# mcu.net
KiCad netlist of a schematic drawn in Altium Designer
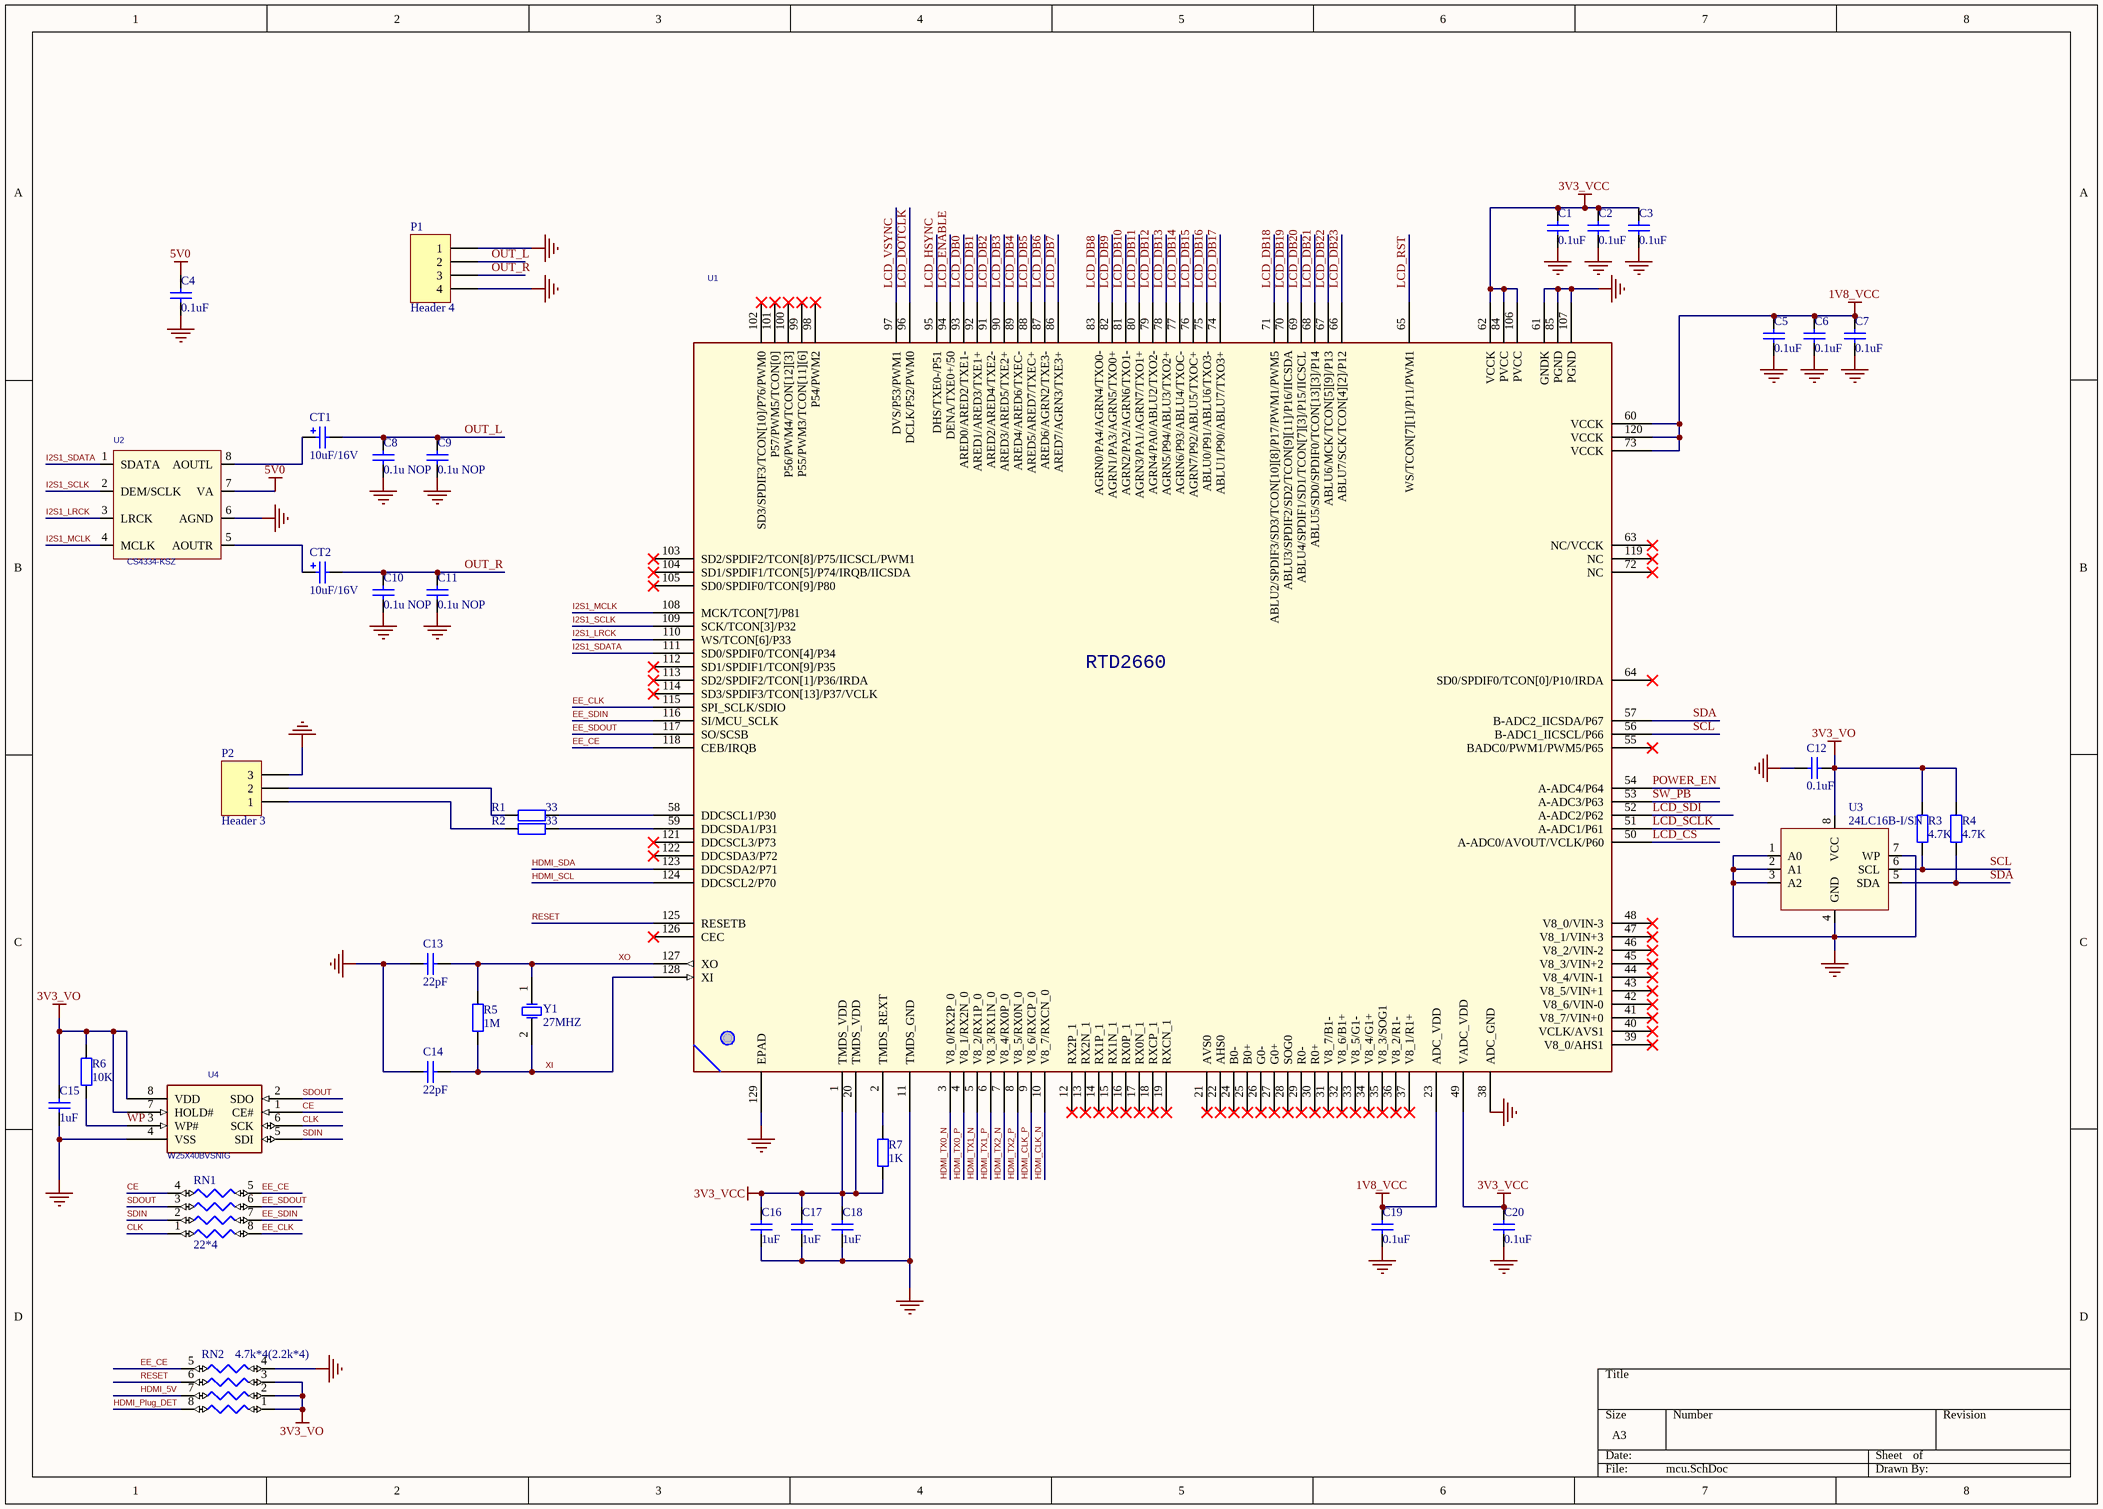
[diagram p0: mcu.SchDoc]

(export (version "E")
  (design (tool "Eeschema 10.0.6"))
  (components
    (comp (ref "C1")
      (value "0.1uF")
      (footprint "0603S-CAP")
      (description "50V/8.2u/0805")
      (fields (field (name "PUBLISHER") "Altium Limited"))
      (libsource (lib "Miscellaneous Devices") (part "Cap"))
    )
    (comp (ref "C2")
      (value "0.1uF")
      (footprint "0603S-CAP")
      (description "50V/8.2u/0805")
      (fields (field (name "PUBLISHER") "Altium Limited"))
      (libsource (lib "Miscellaneous Devices") (part "Cap"))
    )
    (comp (ref "C3")
      (value "0.1uF")
      (footprint "0603S-CAP")
      (description "50V/8.2u/0805")
      (fields (field (name "PUBLISHER") "Altium Limited"))
      (libsource (lib "Miscellaneous Devices") (part "Cap"))
    )
    (comp (ref "C4")
      (value "0.1uF")
      (footprint "0603S-CAP")
      (description "50V/8.2u/0805")
      (fields (field (name "PUBLISHER") "Altium Limited"))
      (libsource (lib "Miscellaneous Devices") (part "Cap"))
    )
    (comp (ref "C5")
      (value "0.1uF")
      (footprint "0603S-CAP")
      (description "50V/8.2u/0805")
      (fields (field (name "PUBLISHER") "Altium Limited"))
      (libsource (lib "Miscellaneous Devices") (part "Cap"))
    )
    (comp (ref "C6")
      (value "0.1uF")
      (footprint "0603S-CAP")
      (description "50V/8.2u/0805")
      (fields (field (name "PUBLISHER") "Altium Limited"))
      (libsource (lib "Miscellaneous Devices") (part "Cap"))
    )
    (comp (ref "C7")
      (value "0.1uF")
      (footprint "0603S-CAP")
      (description "50V/8.2u/0805")
      (fields (field (name "PUBLISHER") "Altium Limited"))
      (libsource (lib "Miscellaneous Devices") (part "Cap"))
    )
    (comp (ref "C8")
      (value "0.1u NOP")
      (footprint "0603S-CAP")
      (description "50V/8.2u/0805")
      (fields (field (name "PUBLISHER") "Altium Limited"))
      (libsource (lib "Miscellaneous Devices") (part "Cap"))
    )
    (comp (ref "C9")
      (value "0.1u NOP")
      (footprint "0603S-CAP")
      (description "50V/8.2u/0805")
      (fields (field (name "PUBLISHER") "Altium Limited"))
      (libsource (lib "Miscellaneous Devices") (part "Cap"))
    )
    (comp (ref "C10")
      (value "0.1u NOP")
      (footprint "0603S-CAP")
      (description "50V/8.2u/0805")
      (fields (field (name "PUBLISHER") "Altium Limited"))
      (libsource (lib "Miscellaneous Devices") (part "Cap"))
    )
    (comp (ref "C11")
      (value "0.1u NOP")
      (footprint "0603S-CAP")
      (description "50V/8.2u/0805")
      (fields (field (name "PUBLISHER") "Altium Limited"))
      (libsource (lib "Miscellaneous Devices") (part "Cap"))
    )
    (comp (ref "C12")
      (value "0.1uF")
      (footprint "0603S-CAP")
      (description "CAP SMT 0.1uF 16V X7R")
      (fields
        (field (name "2. MANUFACTURERE PART NUMBER") "C0805C104K4RACTU")
        (field (name "8. ALTERNATE PART") "any")
      )
      (libsource (lib "Peeple_eval") (part "CAP SMT 0.1uF 16V X7R"))
    )
    (comp (ref "C13")
      (value "22pF")
      (footprint "0603S-CAP")
      (description "50V/8.2u/0805")
      (fields (field (name "PUBLISHER") "Altium Limited"))
      (libsource (lib "Miscellaneous Devices") (part "Cap"))
    )
    (comp (ref "C14")
      (value "22pF")
      (footprint "0603S-CAP")
      (description "50V/8.2u/0805")
      (fields (field (name "PUBLISHER") "Altium Limited"))
      (libsource (lib "Miscellaneous Devices") (part "Cap"))
    )
    (comp (ref "C15")
      (value "1uF")
      (footprint "0603S-CAP")
      (description "50V/8.2u/0805")
      (fields (field (name "PUBLISHER") "Altium Limited"))
      (libsource (lib "Miscellaneous Devices") (part "Cap"))
    )
    (comp (ref "C16")
      (value "1uF")
      (footprint "0603S-CAP")
      (description "50V/8.2u/0805")
      (fields (field (name "PUBLISHER") "Altium Limited"))
      (libsource (lib "Miscellaneous Devices") (part "Cap"))
    )
    (comp (ref "C17")
      (value "1uF")
      (footprint "0603S-CAP")
      (description "50V/8.2u/0805")
      (fields (field (name "PUBLISHER") "Altium Limited"))
      (libsource (lib "Miscellaneous Devices") (part "Cap"))
    )
    (comp (ref "C18")
      (value "1uF")
      (footprint "0603S-CAP")
      (description "50V/8.2u/0805")
      (fields (field (name "PUBLISHER") "Altium Limited"))
      (libsource (lib "Miscellaneous Devices") (part "Cap"))
    )
    (comp (ref "C19")
      (value "0.1uF")
      (footprint "0603S-CAP")
      (description "50V/8.2u/0805")
      (fields (field (name "PUBLISHER") "Altium Limited"))
      (libsource (lib "Miscellaneous Devices") (part "Cap"))
    )
    (comp (ref "C20")
      (value "0.1uF")
      (footprint "0603S-CAP")
      (description "50V/8.2u/0805")
      (fields (field (name "PUBLISHER") "Altium Limited"))
      (libsource (lib "Miscellaneous Devices") (part "Cap"))
    )
    (comp (ref "CT1")
      (value "10uF/16V")
      (footprint "钽电容（A型）")
      (description "Polarized Capacitor (Axial)")
      (fields (field (name "PUBLISHER") "Altium Limited"))
      (libsource (lib "Miscellaneous Devices") (part "Cap Pol2"))
    )
    (comp (ref "CT2")
      (value "10uF/16V")
      (footprint "钽电容（A型）")
      (description "Polarized Capacitor (Axial)")
      (fields (field (name "PUBLISHER") "Altium Limited"))
      (libsource (lib "Miscellaneous Devices") (part "Cap Pol2"))
    )
    (comp (ref "P1")
      (value "Header 4")
      (footprint "PJ-342")
      (description "Header, 4-Pin")
      (fields (field (name "PUBLISHER") "Altium Limited"))
      (libsource (lib "Miscellaneous Connectors") (part "Header 4"))
    )
    (comp (ref "P2")
      (value "Header 3")
      (footprint "smt1X3")
      (description "Header, 3-Pin")
      (fields (field (name "PUBLISHER") "Altium Limited"))
      (libsource (lib "Miscellaneous Connectors") (part "Header 3"))
    )
    (comp (ref "R1")
      (value "33")
      (footprint "0603S-RES")
      (description "Resistor")
      (fields (field (name "PUBLISHER") "Altium Limited"))
      (libsource (lib "DM642") (part "Res2"))
    )
    (comp (ref "R2")
      (value "33")
      (footprint "0603S-RES")
      (description "Resistor")
      (fields (field (name "PUBLISHER") "Altium Limited"))
      (libsource (lib "DM642") (part "Res2"))
    )
    (comp (ref "R3")
      (value "4.7K")
      (footprint "0603S-RES")
      (description "Resistor")
      (fields (field (name "PUBLISHER") "Altium Limited"))
      (libsource (lib "") (part "Res2_1"))
    )
    (comp (ref "R4")
      (value "4.7K")
      (footprint "0603S-RES")
      (description "Resistor")
      (fields (field (name "PUBLISHER") "Altium Limited"))
      (libsource (lib "") (part "Res2_1"))
    )
    (comp (ref "R5")
      (value "1M")
      (footprint "0603S-RES")
      (description "Resistor")
      (fields (field (name "PUBLISHER") "Altium Limited"))
      (libsource (lib "") (part "Res2_1"))
    )
    (comp (ref "R6")
      (value "10K")
      (footprint "0603S-RES")
      (description "Resistor")
      (fields (field (name "PUBLISHER") "Altium Limited"))
      (libsource (lib "") (part "Res2_1"))
    )
    (comp (ref "R7")
      (value "1K")
      (footprint "0603S-RES")
      (description "Resistor")
      (fields (field (name "PUBLISHER") "Altium Limited"))
      (libsource (lib "") (part "Res2_1"))
    )
    (comp (ref "RN1") (value "22*4") (footprint "NC06-4") (libsource (lib "*") (part "RN4")))
    (comp (ref "RN2") (value "4.7k*4(2.2k*4)") (footprint "NC06-4") (libsource (lib "*") (part "RN4")))
    (comp (ref "U1")
      (value "RTD2660H")
      (footprint "LQFP128_P0_5_22X16_EPAD")
      (fields (field (name "PART NUMBER") "21-D004978"))
      (libsource (lib "*") (part "RTD2523_10"))
    )
    (comp (ref "U2")
      (value "CS4334-KSZ")
      (footprint "SOIC-8N")
      (fields (field (name "PART NUMBER") "19-D005021"))
      (libsource (lib "UC-410") (part "CS4334-KSZ"))
    )
    (comp (ref "U3")
      (value "24LC16B-I/SN")
      (footprint "SOIC-8N")
      (description "IC EEPROM 64KBIT 400KHZ 8SOIC")
      (fields
        (field (name "MANUFACTURER") "Microchip Technology")
        (field (name "MANUFACTURER PART NUMBER") "24LC64-I/SN")
      )
      (libsource (lib "Schlib1") (part "24LC64-I/SN"))
    )
    (comp (ref "U4")
      (value "W25X40BVSNIG")
      (footprint "SOIC-8N")
      (fields (field (name "PART NUMBER") "19-D004782"))
      (libsource (lib "*") (part "24C08_1"))
    )
    (comp (ref "Y1")
      (value "27MHZ")
      (footprint "XTAL-SMT")
      (description "Crystal, CRYSTAL 32.768KHZ 6PF SMD")
      (fields
        (field (name "2. MANUFACTURERE PART NUMBER") "ABS07-120-32.768KHZ-T")
        (field (name "4. SUPPLIER PART NUMBER") "535-11937-1-ND")
      )
      (libsource (lib "Peeple_eval") (part "XTAL 32.768KHZ"))
    )
  )
  (nets
    (net (code "1") (name "/CE") (class "Default")
      (node (ref "RN1") (pin "4") (pinfunction "4_4") (pintype "bidirectional"))
      (node (ref "U4") (pin "1") (pinfunction "CE#_1") (pintype "input"))
    )
    (net (code "2") (name "/CLK") (class "Default")
      (node (ref "RN1") (pin "1") (pinfunction "1_1") (pintype "bidirectional"))
      (node (ref "U4") (pin "6") (pinfunction "SCK_6") (pintype "bidirectional"))
    )
    (net (code "3") (name "/EE_CE") (class "Default")
      (node (ref "RN1") (pin "5") (pinfunction "5_5") (pintype "bidirectional"))
      (node (ref "RN2") (pin "5") (pinfunction "5_5") (pintype "bidirectional"))
      (node (ref "U1") (pin "118") (pinfunction "CEB/IRQB_118") (pintype "passive"))
    )
    (net (code "4") (name "/EE_CLK") (class "Default")
      (node (ref "RN1") (pin "8") (pinfunction "8_8") (pintype "bidirectional"))
      (node (ref "U1") (pin "115") (pinfunction "SPI_SCLK/SDIO_115") (pintype "passive"))
    )
    (net (code "5") (name "/EE_SDIN") (class "Default")
      (node (ref "RN1") (pin "7") (pinfunction "7_7") (pintype "bidirectional"))
      (node (ref "U1") (pin "116") (pinfunction "SI/MCU_SCLK_116") (pintype "passive"))
    )
    (net (code "6") (name "/EE_SDOUT") (class "Default")
      (node (ref "RN1") (pin "6") (pinfunction "6_6") (pintype "bidirectional"))
      (node (ref "U1") (pin "117") (pinfunction "SO/SCSB_117") (pintype "passive"))
    )
    (net (code "7") (name "/HDMI_5V") (class "Default")
      (node (ref "RN2") (pin "7") (pinfunction "7_7") (pintype "bidirectional"))
    )
    (net (code "8") (name "/HDMI_CLK_N") (class "Default")
      (node (ref "U1") (pin "10") (pinfunction "V8_7/RXCN_0_10") (pintype "passive"))
    )
    (net (code "9") (name "/HDMI_CLK_P") (class "Default")
      (node (ref "U1") (pin "9") (pinfunction "V8_6/RXCP_0_9") (pintype "passive"))
    )
    (net (code "10") (name "/HDMI_Plug_DET") (class "Default")
      (node (ref "RN2") (pin "8") (pinfunction "8_8") (pintype "bidirectional"))
    )
    (net (code "11") (name "/HDMI_SCL") (class "Default")
      (node (ref "U1") (pin "124") (pinfunction "DDCSCL2/P70_124") (pintype "passive"))
    )
    (net (code "12") (name "/HDMI_SDA") (class "Default")
      (node (ref "U1") (pin "123") (pinfunction "DDCSDA2/P71_123") (pintype "passive"))
    )
    (net (code "13") (name "/HDMI_TX0_N") (class "Default")
      (node (ref "U1") (pin "3") (pinfunction "V8_0/RX2P_0_3") (pintype "passive"))
    )
    (net (code "14") (name "/HDMI_TX0_P") (class "Default")
      (node (ref "U1") (pin "4") (pinfunction "V8_1/RX2N_0_4") (pintype "passive"))
    )
    (net (code "15") (name "/HDMI_TX1_N") (class "Default")
      (node (ref "U1") (pin "5") (pinfunction "V8_2/RX1P_0_5") (pintype "passive"))
    )
    (net (code "16") (name "/HDMI_TX1_P") (class "Default")
      (node (ref "U1") (pin "6") (pinfunction "V8_3/RX1N_0_6") (pintype "passive"))
    )
    (net (code "17") (name "/HDMI_TX2_N") (class "Default")
      (node (ref "U1") (pin "7") (pinfunction "V8_4/RX0P_0_7") (pintype "passive"))
    )
    (net (code "18") (name "/HDMI_TX2_P") (class "Default")
      (node (ref "U1") (pin "8") (pinfunction "V8_5/RX0N_0_8") (pintype "passive"))
    )
    (net (code "19") (name "/I2S1_LRCK") (class "Default")
      (node (ref "U1") (pin "110") (pinfunction "WS/TCON[6]/P33_110") (pintype "passive"))
      (node (ref "U2") (pin "3") (pinfunction "LRCK_3") (pintype "passive"))
    )
    (net (code "20") (name "/I2S1_MCLK") (class "Default")
      (node (ref "U1") (pin "108") (pinfunction "MCK/TCON[7]/P81_108") (pintype "passive"))
      (node (ref "U2") (pin "4") (pinfunction "MCLK_4") (pintype "passive"))
    )
    (net (code "21") (name "/I2S1_SCLK") (class "Default")
      (node (ref "U1") (pin "109") (pinfunction "SCK/TCON[3]/P32_109") (pintype "passive"))
      (node (ref "U2") (pin "2") (pinfunction "DEM/SCLK_2") (pintype "passive"))
    )
    (net (code "22") (name "/I2S1_SDATA") (class "Default")
      (node (ref "U1") (pin "111") (pinfunction "SD0/SPDIF0/TCON[4]/P34_111") (pintype "passive"))
      (node (ref "U2") (pin "1") (pinfunction "SDATA_1") (pintype "passive"))
    )
    (net (code "23") (name "/LCD_CS") (class "Default")
      (node (ref "U1") (pin "50") (pinfunction "A-ADC0/AVOUT/VCLK/P60_50") (pintype "passive"))
    )
    (net (code "24") (name "/LCD_DB0") (class "Default")
      (node (ref "U1") (pin "93") (pinfunction "ARED0/ARED2/TXE1-_93") (pintype "passive"))
    )
    (net (code "25") (name "/LCD_DB1") (class "Default")
      (node (ref "U1") (pin "92") (pinfunction "ARED1/ARED3/TXE1+_92") (pintype "passive"))
    )
    (net (code "26") (name "/LCD_DB2") (class "Default")
      (node (ref "U1") (pin "91") (pinfunction "ARED2/ARED4/TXE2-_91") (pintype "passive"))
    )
    (net (code "27") (name "/LCD_DB3") (class "Default")
      (node (ref "U1") (pin "90") (pinfunction "ARED3/ARED5/TXE2+_90") (pintype "passive"))
    )
    (net (code "28") (name "/LCD_DB4") (class "Default")
      (node (ref "U1") (pin "89") (pinfunction "ARED4/ARED6/TXEC-_89") (pintype "passive"))
    )
    (net (code "29") (name "/LCD_DB5") (class "Default")
      (node (ref "U1") (pin "88") (pinfunction "ARED5/ARED7/TXEC+_88") (pintype "passive"))
    )
    (net (code "30") (name "/LCD_DB6") (class "Default")
      (node (ref "U1") (pin "87") (pinfunction "ARED6/AGRN2/TXE3-_87") (pintype "passive"))
    )
    (net (code "31") (name "/LCD_DB7") (class "Default")
      (node (ref "U1") (pin "86") (pinfunction "ARED7/AGRN3/TXE3+_86") (pintype "passive"))
    )
    (net (code "32") (name "/LCD_DB8") (class "Default")
      (node (ref "U1") (pin "83") (pinfunction "AGRN0/PA4/AGRN4/TXO0-_83") (pintype "passive"))
    )
    (net (code "33") (name "/LCD_DB9") (class "Default")
      (node (ref "U1") (pin "82") (pinfunction "AGRN1/PA3/AGRN5/TXO0+_82") (pintype "passive"))
    )
    (net (code "34") (name "/LCD_DB10") (class "Default")
      (node (ref "U1") (pin "81") (pinfunction "AGRN2/PA2/AGRN6/TXO1-_81") (pintype "passive"))
    )
    (net (code "35") (name "/LCD_DB11") (class "Default")
      (node (ref "U1") (pin "80") (pinfunction "AGRN3/PA1/AGRN7/TXO1+_80") (pintype "passive"))
    )
    (net (code "36") (name "/LCD_DB12") (class "Default")
      (node (ref "U1") (pin "79") (pinfunction "AGRN4/PA0/ABLU2/TXO2-_79") (pintype "passive"))
    )
    (net (code "37") (name "/LCD_DB13") (class "Default")
      (node (ref "U1") (pin "78") (pinfunction "AGRN5/P94/ABLU3/TXO2+_78") (pintype "passive"))
    )
    (net (code "38") (name "/LCD_DB14") (class "Default")
      (node (ref "U1") (pin "77") (pinfunction "AGRN6/P93/ABLU4/TXOC-_77") (pintype "passive"))
    )
    (net (code "39") (name "/LCD_DB15") (class "Default")
      (node (ref "U1") (pin "76") (pinfunction "AGRN7/P92/ABLU5/TXOC+_76") (pintype "passive"))
    )
    (net (code "40") (name "/LCD_DB16") (class "Default")
      (node (ref "U1") (pin "75") (pinfunction "ABLU0/P91/ABLU6/TXO3-_75") (pintype "passive"))
    )
    (net (code "41") (name "/LCD_DB17") (class "Default")
      (node (ref "U1") (pin "74") (pinfunction "ABLU1/P90/ABLU7/TXO3+_74") (pintype "passive"))
    )
    (net (code "42") (name "/LCD_DB18") (class "Default")
      (node (ref "U1") (pin "71") (pinfunction "ABLU2/SPDIF3/SD3/TCON[10][8]/P17/PWM1/PWM5_71") (pintype "passive"))
    )
    (net (code "43") (name "/LCD_DB19") (class "Default")
      (node (ref "U1") (pin "70") (pinfunction "ABLU3/SPDIF2/SD2/TCON[9][11]/P16/IICSDA_70") (pintype "passive"))
    )
    (net (code "44") (name "/LCD_DB20") (class "Default")
      (node (ref "U1") (pin "69") (pinfunction "ABLU4/SPDIF1/SD1/TCON[7][3]/P15/IICSCL_69") (pintype "passive"))
    )
    (net (code "45") (name "/LCD_DB21") (class "Default")
      (node (ref "U1") (pin "68") (pinfunction "ABLU5/SD0/SPDIF0/TCON[13][3]/P14_68") (pintype "passive"))
    )
    (net (code "46") (name "/LCD_DB22") (class "Default")
      (node (ref "U1") (pin "67") (pinfunction "ABLU6/MCK/TCON[5][9]/P13_67") (pintype "passive"))
    )
    (net (code "47") (name "/LCD_DB23") (class "Default")
      (node (ref "U1") (pin "66") (pinfunction "ABLU7/SCK/TCON[4][2]/P12_66") (pintype "passive"))
    )
    (net (code "48") (name "/LCD_DOTCLK") (class "Default")
      (node (ref "U1") (pin "96") (pinfunction "DCLK/P52/PWM0_96") (pintype "passive"))
    )
    (net (code "49") (name "/LCD_ENABLE") (class "Default")
      (node (ref "U1") (pin "94") (pinfunction "DENA/TXE0+/50_94") (pintype "passive"))
    )
    (net (code "50") (name "/LCD_HSYNC") (class "Default")
      (node (ref "U1") (pin "95") (pinfunction "DHS/TXE0-/P51_95") (pintype "passive"))
    )
    (net (code "51") (name "/LCD_RST") (class "Default")
      (node (ref "U1") (pin "65") (pinfunction "WS/TCON[7][1]/P11/PWM1_65") (pintype "passive"))
    )
    (net (code "52") (name "/LCD_SCLK") (class "Default")
      (node (ref "U1") (pin "51") (pinfunction "A-ADC1/P61_51") (pintype "passive"))
    )
    (net (code "53") (name "/LCD_SDI") (class "Default")
      (node (ref "U1") (pin "52") (pinfunction "A-ADC2/P62_52") (pintype "passive"))
    )
    (net (code "54") (name "/LCD_VSYNC") (class "Default")
      (node (ref "U1") (pin "97") (pinfunction "DVS/P53/PWM1_97") (pintype "passive"))
    )
    (net (code "55") (name "/OUT_L") (class "Default")
      (node (ref "C8") (pin "2") (pinfunction "2_2") (pintype "passive"))
      (node (ref "C9") (pin "2") (pinfunction "2_2") (pintype "passive"))
      (node (ref "CT1") (pin "2") (pinfunction "2_2") (pintype "passive"))
      (node (ref "P1") (pin "2") (pinfunction "2_2") (pintype "passive"))
    )
    (net (code "56") (name "/OUT_R") (class "Default")
      (node (ref "C10") (pin "2") (pinfunction "2_2") (pintype "passive"))
      (node (ref "C11") (pin "2") (pinfunction "2_2") (pintype "passive"))
      (node (ref "CT2") (pin "2") (pinfunction "2_2") (pintype "passive"))
      (node (ref "P1") (pin "3") (pinfunction "3_3") (pintype "passive"))
    )
    (net (code "57") (name "/POWER_EN") (class "Default")
      (node (ref "U1") (pin "54") (pinfunction "A-ADC4/P64_54") (pintype "passive"))
    )
    (net (code "58") (name "/RESET") (class "Default")
      (node (ref "RN2") (pin "6") (pinfunction "6_6") (pintype "bidirectional"))
      (node (ref "U1") (pin "125") (pinfunction "RESETB_125") (pintype "passive"))
    )
    (net (code "59") (name "/SCL") (class "Default")
      (node (ref "R3") (pin "1") (pinfunction "1_1") (pintype "passive"))
      (node (ref "U1") (pin "56") (pinfunction "B-ADC1_IICSCL/P66_56") (pintype "passive"))
      (node (ref "U3") (pin "6") (pinfunction "SCL_6") (pintype "passive"))
    )
    (net (code "60") (name "/SDA") (class "Default")
      (node (ref "R4") (pin "1") (pinfunction "1_1") (pintype "passive"))
      (node (ref "U1") (pin "57") (pinfunction "B-ADC2_IICSDA/P67_57") (pintype "passive"))
      (node (ref "U3") (pin "5") (pinfunction "SDA_5") (pintype "passive"))
    )
    (net (code "61") (name "/SDIN") (class "Default")
      (node (ref "RN1") (pin "2") (pinfunction "2_2") (pintype "bidirectional"))
      (node (ref "U4") (pin "5") (pinfunction "SDI_5") (pintype "bidirectional"))
    )
    (net (code "62") (name "/SDOUT") (class "Default")
      (node (ref "RN1") (pin "3") (pinfunction "3_3") (pintype "bidirectional"))
      (node (ref "U4") (pin "2") (pinfunction "SDO_2") (pintype "input"))
    )
    (net (code "63") (name "/SW_PB") (class "Default")
      (node (ref "U1") (pin "53") (pinfunction "A-ADC3/P63_53") (pintype "passive"))
    )
    (net (code "64") (name "/WP") (class "Default")
      (node (ref "R6") (pin "1") (pinfunction "1_1") (pintype "passive"))
      (node (ref "U4") (pin "3") (pinfunction "WP#_3") (pintype "input"))
    )
    (net (code "65") (name "/XI") (class "Default")
      (node (ref "C14") (pin "1") (pinfunction "1_1") (pintype "passive"))
      (node (ref "R5") (pin "1") (pinfunction "1_1") (pintype "passive"))
      (node (ref "U1") (pin "128") (pinfunction "XI_128") (pintype "input"))
      (node (ref "Y1") (pin "2") (pinfunction "OSC2_2") (pintype "passive"))
    )
    (net (code "66") (name "/XO") (class "Default")
      (node (ref "C13") (pin "1") (pinfunction "1_1") (pintype "passive"))
      (node (ref "R5") (pin "2") (pinfunction "2_2") (pintype "passive"))
      (node (ref "U1") (pin "127") (pinfunction "XO_127") (pintype "output"))
      (node (ref "Y1") (pin "1") (pinfunction "OSC1_1") (pintype "passive"))
    )
    (net (code "67") (name "1V8_VCC") (class "Default")
      (node (ref "C19") (pin "2") (pinfunction "2_2") (pintype "passive"))
      (node (ref "C5") (pin "2") (pinfunction "2_2") (pintype "passive"))
      (node (ref "C6") (pin "2") (pinfunction "2_2") (pintype "passive"))
      (node (ref "C7") (pin "2") (pinfunction "2_2") (pintype "passive"))
      (node (ref "U1") (pin "120") (pinfunction "VCCK_120") (pintype "power_in"))
      (node (ref "U1") (pin "23") (pinfunction "ADC_VDD_23") (pintype "power_in"))
      (node (ref "U1") (pin "60") (pinfunction "VCCK_60") (pintype "power_in"))
      (node (ref "U1") (pin "73") (pinfunction "VCCK_73") (pintype "power_in"))
    )
    (net (code "68") (name "3V3_VCC") (class "Default")
      (node (ref "C1") (pin "2") (pinfunction "2_2") (pintype "passive"))
      (node (ref "C16") (pin "2") (pinfunction "2_2") (pintype "passive"))
      (node (ref "C17") (pin "2") (pinfunction "2_2") (pintype "passive"))
      (node (ref "C18") (pin "2") (pinfunction "2_2") (pintype "passive"))
      (node (ref "C2") (pin "2") (pinfunction "2_2") (pintype "passive"))
      (node (ref "C20") (pin "2") (pinfunction "2_2") (pintype "passive"))
      (node (ref "C3") (pin "2") (pinfunction "2_2") (pintype "passive"))
      (node (ref "R7") (pin "1") (pinfunction "1_1") (pintype "passive"))
      (node (ref "U1") (pin "1") (pinfunction "TMDS_VDD_1") (pintype "power_in"))
      (node (ref "U1") (pin "106") (pinfunction "PVCC_106") (pintype "power_in"))
      (node (ref "U1") (pin "20") (pinfunction "TMDS_VDD_20") (pintype "power_in"))
      (node (ref "U1") (pin "49") (pinfunction "VADC_VDD_49") (pintype "power_in"))
      (node (ref "U1") (pin "62") (pinfunction "VCCK_62") (pintype "power_in"))
      (node (ref "U1") (pin "84") (pinfunction "PVCC_84") (pintype "power_in"))
    )
    (net (code "69") (name "3V3_VO") (class "Default")
      (node (ref "C12") (pin "2") (pinfunction "2_2") (pintype "passive"))
      (node (ref "C15") (pin "2") (pinfunction "2_2") (pintype "passive"))
      (node (ref "R3") (pin "2") (pinfunction "2_2") (pintype "passive"))
      (node (ref "R4") (pin "2") (pinfunction "2_2") (pintype "passive"))
      (node (ref "R6") (pin "2") (pinfunction "2_2") (pintype "passive"))
      (node (ref "RN2") (pin "1") (pinfunction "1_1") (pintype "bidirectional"))
      (node (ref "RN2") (pin "2") (pinfunction "2_2") (pintype "bidirectional"))
      (node (ref "RN2") (pin "3") (pinfunction "3_3") (pintype "bidirectional"))
      (node (ref "U3") (pin "8") (pinfunction "VCC_8") (pintype "passive"))
      (node (ref "U4") (pin "7") (pinfunction "HOLD#_7") (pintype "input"))
      (node (ref "U4") (pin "8") (pinfunction "VDD_8") (pintype "power_in"))
    )
    (net (code "70") (name "5V0") (class "Default")
      (node (ref "C4") (pin "2") (pinfunction "2_2") (pintype "passive"))
      (node (ref "U2") (pin "7") (pinfunction "VA_7") (pintype "passive"))
    )
    (net (code "71") (name "GND") (class "Default")
      (node (ref "C1") (pin "1") (pinfunction "1_1") (pintype "passive"))
      (node (ref "C10") (pin "1") (pinfunction "1_1") (pintype "passive"))
      (node (ref "C11") (pin "1") (pinfunction "1_1") (pintype "passive"))
      (node (ref "C12") (pin "1") (pinfunction "1_1") (pintype "passive"))
      (node (ref "C13") (pin "2") (pinfunction "2_2") (pintype "passive"))
      (node (ref "C14") (pin "2") (pinfunction "2_2") (pintype "passive"))
      (node (ref "C15") (pin "1") (pinfunction "1_1") (pintype "passive"))
      (node (ref "C16") (pin "1") (pinfunction "1_1") (pintype "passive"))
      (node (ref "C17") (pin "1") (pinfunction "1_1") (pintype "passive"))
      (node (ref "C18") (pin "1") (pinfunction "1_1") (pintype "passive"))
      (node (ref "C19") (pin "1") (pinfunction "1_1") (pintype "passive"))
      (node (ref "C2") (pin "1") (pinfunction "1_1") (pintype "passive"))
      (node (ref "C20") (pin "1") (pinfunction "1_1") (pintype "passive"))
      (node (ref "C3") (pin "1") (pinfunction "1_1") (pintype "passive"))
      (node (ref "C4") (pin "1") (pinfunction "1_1") (pintype "passive"))
      (node (ref "C5") (pin "1") (pinfunction "1_1") (pintype "passive"))
      (node (ref "C6") (pin "1") (pinfunction "1_1") (pintype "passive"))
      (node (ref "C7") (pin "1") (pinfunction "1_1") (pintype "passive"))
      (node (ref "C8") (pin "1") (pinfunction "1_1") (pintype "passive"))
      (node (ref "C9") (pin "1") (pinfunction "1_1") (pintype "passive"))
      (node (ref "P1") (pin "1") (pinfunction "1_1") (pintype "passive"))
      (node (ref "P1") (pin "4") (pinfunction "4_4") (pintype "passive"))
      (node (ref "P2") (pin "3") (pinfunction "3_3") (pintype "passive"))
      (node (ref "RN2") (pin "4") (pinfunction "4_4") (pintype "bidirectional"))
      (node (ref "U1") (pin "107") (pinfunction "PGND_107") (pintype "power_in"))
      (node (ref "U1") (pin "11") (pinfunction "TMDS_GND_11") (pintype "power_in"))
      (node (ref "U1") (pin "129") (pinfunction "EPAD_129") (pintype "passive"))
      (node (ref "U1") (pin "38") (pinfunction "ADC_GND_38") (pintype "power_in"))
      (node (ref "U1") (pin "61") (pinfunction "GNDK_61") (pintype "power_in"))
      (node (ref "U1") (pin "85") (pinfunction "PGND_85") (pintype "power_in"))
      (node (ref "U2") (pin "6") (pinfunction "AGND_6") (pintype "passive"))
      (node (ref "U3") (pin "1") (pinfunction "A0_1") (pintype "passive"))
      (node (ref "U3") (pin "2") (pinfunction "A1_2") (pintype "passive"))
      (node (ref "U3") (pin "3") (pinfunction "A2_3") (pintype "passive"))
      (node (ref "U3") (pin "4") (pinfunction "GND_4") (pintype "passive"))
      (node (ref "U3") (pin "7") (pinfunction "WP_7") (pintype "passive"))
      (node (ref "U4") (pin "4") (pinfunction "VSS_4") (pintype "power_in"))
    )
    (net (code "72") (name "Net-(P2-Pad1)") (class "Default")
      (node (ref "P2") (pin "1") (pinfunction "1_1") (pintype "passive"))
      (node (ref "R2") (pin "2") (pinfunction "2_2") (pintype "passive"))
    )
    (net (code "73") (name "Net-(P2-Pad2)") (class "Default")
      (node (ref "P2") (pin "2") (pinfunction "2_2") (pintype "passive"))
      (node (ref "R1") (pin "2") (pinfunction "2_2") (pintype "passive"))
    )
    (net (code "74") (name "Net-(U1-DDCSCL1{slash}P30)") (class "Default")
      (node (ref "R1") (pin "1") (pinfunction "1_1") (pintype "passive"))
      (node (ref "U1") (pin "58") (pinfunction "DDCSCL1/P30_58") (pintype "passive"))
    )
    (net (code "75") (name "Net-(U1-DDCSDA1{slash}P31)") (class "Default")
      (node (ref "R2") (pin "1") (pinfunction "1_1") (pintype "passive"))
      (node (ref "U1") (pin "59") (pinfunction "DDCSDA1/P31_59") (pintype "passive"))
    )
    (net (code "76") (name "Net-(U1-TMDS_REXT)") (class "Default")
      (node (ref "R7") (pin "2") (pinfunction "2_2") (pintype "passive"))
      (node (ref "U1") (pin "2") (pinfunction "TMDS_REXT_2") (pintype "passive"))
    )
    (net (code "77") (name "Net-(U2-AOUTL)") (class "Default")
      (node (ref "CT1") (pin "1") (pinfunction "1_1") (pintype "passive"))
      (node (ref "U2") (pin "8") (pinfunction "AOUTL_8") (pintype "passive"))
    )
    (net (code "78") (name "Net-(U2-AOUTR)") (class "Default")
      (node (ref "CT2") (pin "1") (pinfunction "1_1") (pintype "passive"))
      (node (ref "U2") (pin "5") (pinfunction "AOUTR_5") (pintype "passive"))
    )
    (net (code "79") (name "unconnected-(U1-AHS0-Pad22)") (class "Default")
      (node (ref "U1") (pin "22") (pinfunction "AHS0_22") (pintype "passive+no_connect"))
    )
    (net (code "80") (name "unconnected-(U1-AVS0-Pad21)") (class "Default")
      (node (ref "U1") (pin "21") (pinfunction "AVS0_21") (pintype "passive+no_connect"))
    )
    (net (code "81") (name "unconnected-(U1-B0+-Pad25)") (class "Default")
      (node (ref "U1") (pin "25") (pinfunction "B0+_25") (pintype "passive+no_connect"))
    )
    (net (code "82") (name "unconnected-(U1-B0--Pad24)") (class "Default")
      (node (ref "U1") (pin "24") (pinfunction "B0-_24") (pintype "passive+no_connect"))
    )
    (net (code "83") (name "unconnected-(U1-BADC0{slash}PWM1{slash}PWM5{slash}P65-Pad55)") (class "Default")
      (node (ref "U1") (pin "55") (pinfunction "BADC0/PWM1/PWM5/P65_55") (pintype "passive+no_connect"))
    )
    (net (code "84") (name "unconnected-(U1-CEC-Pad126)") (class "Default")
      (node (ref "U1") (pin "126") (pinfunction "CEC_126") (pintype "passive+no_connect"))
    )
    (net (code "85") (name "unconnected-(U1-DDCSCL3{slash}P73-Pad121)") (class "Default")
      (node (ref "U1") (pin "121") (pinfunction "DDCSCL3/P73_121") (pintype "passive+no_connect"))
    )
    (net (code "86") (name "unconnected-(U1-DDCSDA3{slash}P72-Pad122)") (class "Default")
      (node (ref "U1") (pin "122") (pinfunction "DDCSDA3/P72_122") (pintype "passive+no_connect"))
    )
    (net (code "87") (name "unconnected-(U1-G0+-Pad27)") (class "Default")
      (node (ref "U1") (pin "27") (pinfunction "G0+_27") (pintype "passive+no_connect"))
    )
    (net (code "88") (name "unconnected-(U1-G0--Pad26)") (class "Default")
      (node (ref "U1") (pin "26") (pinfunction "G0-_26") (pintype "passive+no_connect"))
    )
    (net (code "89") (name "unconnected-(U1-NC-Pad72)") (class "Default")
      (node (ref "U1") (pin "72") (pinfunction "NC_72") (pintype "passive+no_connect"))
    )
    (net (code "90") (name "unconnected-(U1-NC-Pad119)") (class "Default")
      (node (ref "U1") (pin "119") (pinfunction "NC_119") (pintype "passive+no_connect"))
    )
    (net (code "91") (name "unconnected-(U1-NC{slash}VCCK-Pad63)") (class "Default")
      (node (ref "U1") (pin "63") (pinfunction "NC/VCCK_63") (pintype "passive+no_connect"))
    )
    (net (code "92") (name "unconnected-(U1-P54{slash}PWM2-Pad98)") (class "Default")
      (node (ref "U1") (pin "98") (pinfunction "P54/PWM2_98") (pintype "passive+no_connect"))
    )
    (net (code "93") (name "unconnected-(U1-P55{slash}PWM3{slash}TCON[11][6]-Pad99)") (class "Default")
      (node (ref "U1") (pin "99") (pinfunction "P55/PWM3/TCON[11][6]_99") (pintype "passive+no_connect"))
    )
    (net (code "94") (name "unconnected-(U1-P56{slash}PWM4{slash}TCON[12][3]-Pad100)") (class "Default")
      (node (ref "U1") (pin "100") (pinfunction "P56/PWM4/TCON[12][3]_100") (pintype "passive+no_connect"))
    )
    (net (code "95") (name "unconnected-(U1-P57{slash}PWM5{slash}TCON[0]-Pad101)") (class "Default")
      (node (ref "U1") (pin "101") (pinfunction "P57/PWM5/TCON[0]_101") (pintype "passive+no_connect"))
    )
    (net (code "96") (name "unconnected-(U1-R0+-Pad30)") (class "Default")
      (node (ref "U1") (pin "30") (pinfunction "R0+_30") (pintype "passive+no_connect"))
    )
    (net (code "97") (name "unconnected-(U1-R0--Pad29)") (class "Default")
      (node (ref "U1") (pin "29") (pinfunction "R0-_29") (pintype "passive+no_connect"))
    )
    (net (code "98") (name "unconnected-(U1-RX0N_1-Pad17)") (class "Default")
      (node (ref "U1") (pin "17") (pinfunction "RX0N_1_17") (pintype "passive+no_connect"))
    )
    (net (code "99") (name "unconnected-(U1-RX0P_1-Pad16)") (class "Default")
      (node (ref "U1") (pin "16") (pinfunction "RX0P_1_16") (pintype "passive+no_connect"))
    )
    (net (code "100") (name "unconnected-(U1-RX1N_1-Pad15)") (class "Default")
      (node (ref "U1") (pin "15") (pinfunction "RX1N_1_15") (pintype "passive+no_connect"))
    )
    (net (code "101") (name "unconnected-(U1-RX1P_1-Pad14)") (class "Default")
      (node (ref "U1") (pin "14") (pinfunction "RX1P_1_14") (pintype "passive+no_connect"))
    )
    (net (code "102") (name "unconnected-(U1-RX2N_1-Pad13)") (class "Default")
      (node (ref "U1") (pin "13") (pinfunction "RX2N_1_13") (pintype "passive+no_connect"))
    )
    (net (code "103") (name "unconnected-(U1-RX2P_1-Pad12)") (class "Default")
      (node (ref "U1") (pin "12") (pinfunction "RX2P_1_12") (pintype "passive+no_connect"))
    )
    (net (code "104") (name "unconnected-(U1-RXCN_1-Pad19)") (class "Default")
      (node (ref "U1") (pin "19") (pinfunction "RXCN_1_19") (pintype "passive+no_connect"))
    )
    (net (code "105") (name "unconnected-(U1-RXCP_1-Pad18)") (class "Default")
      (node (ref "U1") (pin "18") (pinfunction "RXCP_1_18") (pintype "passive+no_connect"))
    )
    (net (code "106") (name "unconnected-(U1-SD0{slash}SPDIF0{slash}TCON[0]{slash}P10{slash}IRDA-Pad64)") (class "Default")
      (node (ref "U1") (pin "64") (pinfunction "SD0/SPDIF0/TCON[0]/P10/IRDA_64") (pintype "passive+no_connect"))
    )
    (net (code "107") (name "unconnected-(U1-SD0{slash}SPDIF0{slash}TCON[9]{slash}P80-Pad105)") (class "Default")
      (node (ref "U1") (pin "105") (pinfunction "SD0/SPDIF0/TCON[9]/P80_105") (pintype "passive+no_connect"))
    )
    (net (code "108") (name "unconnected-(U1-SD1{slash}SPDIF1{slash}TCON[5]{slash}P74{slash}IRQB{slash}IICSDA-Pad104)") (class "Default")
      (node (ref "U1") (pin "104") (pinfunction "SD1/SPDIF1/TCON[5]/P74/IRQB/IICSDA_104") (pintype "passive+no_connect"))
    )
    (net (code "109") (name "unconnected-(U1-SD1{slash}SPDIF1{slash}TCON[9]{slash}P35-Pad112)") (class "Default")
      (node (ref "U1") (pin "112") (pinfunction "SD1/SPDIF1/TCON[9]/P35_112") (pintype "passive+no_connect"))
    )
    (net (code "110") (name "unconnected-(U1-SD2{slash}SPDIF2{slash}TCON[1]{slash}P36{slash}IRDA-Pad113)") (class "Default")
      (node (ref "U1") (pin "113") (pinfunction "SD2/SPDIF2/TCON[1]/P36/IRDA_113") (pintype "passive+no_connect"))
    )
    (net (code "111") (name "unconnected-(U1-SD2{slash}SPDIF2{slash}TCON[8]{slash}P75{slash}IICSCL{slash}PWM1-Pad103)") (class "Default")
      (node (ref "U1") (pin "103") (pinfunction "SD2/SPDIF2/TCON[8]/P75/IICSCL/PWM1_103") (pintype "passive+no_connect"))
    )
    (net (code "112") (name "unconnected-(U1-SD3{slash}SPDIF3{slash}TCON[10]{slash}P76{slash}PWM0-Pad102)") (class "Default")
      (node (ref "U1") (pin "102") (pinfunction "SD3/SPDIF3/TCON[10]/P76/PWM0_102") (pintype "passive+no_connect"))
    )
    (net (code "113") (name "unconnected-(U1-SD3{slash}SPDIF3{slash}TCON[13]{slash}P37{slash}VCLK-Pad114)") (class "Default")
      (node (ref "U1") (pin "114") (pinfunction "SD3/SPDIF3/TCON[13]/P37/VCLK_114") (pintype "passive+no_connect"))
    )
    (net (code "114") (name "unconnected-(U1-SOG0-Pad28)") (class "Default")
      (node (ref "U1") (pin "28") (pinfunction "SOG0_28") (pintype "passive+no_connect"))
    )
    (net (code "115") (name "unconnected-(U1-V8_0{slash}AHS1-Pad39)") (class "Default")
      (node (ref "U1") (pin "39") (pinfunction "V8_0/AHS1_39") (pintype "passive+no_connect"))
    )
    (net (code "116") (name "unconnected-(U1-V8_0{slash}VIN-3-Pad48)") (class "Default")
      (node (ref "U1") (pin "48") (pinfunction "V8_0/VIN-3_48") (pintype "passive+no_connect"))
    )
    (net (code "117") (name "unconnected-(U1-V8_1{slash}R1+-Pad37)") (class "Default")
      (node (ref "U1") (pin "37") (pinfunction "V8_1/R1+_37") (pintype "passive+no_connect"))
    )
    (net (code "118") (name "unconnected-(U1-V8_1{slash}VIN+3-Pad47)") (class "Default")
      (node (ref "U1") (pin "47") (pinfunction "V8_1/VIN+3_47") (pintype "passive+no_connect"))
    )
    (net (code "119") (name "unconnected-(U1-V8_2{slash}R1--Pad36)") (class "Default")
      (node (ref "U1") (pin "36") (pinfunction "V8_2/R1-_36") (pintype "passive+no_connect"))
    )
    (net (code "120") (name "unconnected-(U1-V8_2{slash}VIN-2-Pad46)") (class "Default")
      (node (ref "U1") (pin "46") (pinfunction "V8_2/VIN-2_46") (pintype "passive+no_connect"))
    )
    (net (code "121") (name "unconnected-(U1-V8_3{slash}SOG1-Pad35)") (class "Default")
      (node (ref "U1") (pin "35") (pinfunction "V8_3/SOG1_35") (pintype "passive+no_connect"))
    )
    (net (code "122") (name "unconnected-(U1-V8_3{slash}VIN+2-Pad45)") (class "Default")
      (node (ref "U1") (pin "45") (pinfunction "V8_3/VIN+2_45") (pintype "passive+no_connect"))
    )
    (net (code "123") (name "unconnected-(U1-V8_4{slash}G1+-Pad34)") (class "Default")
      (node (ref "U1") (pin "34") (pinfunction "V8_4/G1+_34") (pintype "passive+no_connect"))
    )
    (net (code "124") (name "unconnected-(U1-V8_4{slash}VIN-1-Pad44)") (class "Default")
      (node (ref "U1") (pin "44") (pinfunction "V8_4/VIN-1_44") (pintype "passive+no_connect"))
    )
    (net (code "125") (name "unconnected-(U1-V8_5{slash}G1--Pad33)") (class "Default")
      (node (ref "U1") (pin "33") (pinfunction "V8_5/G1-_33") (pintype "passive+no_connect"))
    )
    (net (code "126") (name "unconnected-(U1-V8_5{slash}VIN+1-Pad43)") (class "Default")
      (node (ref "U1") (pin "43") (pinfunction "V8_5/VIN+1_43") (pintype "passive+no_connect"))
    )
    (net (code "127") (name "unconnected-(U1-V8_6{slash}B1+-Pad32)") (class "Default")
      (node (ref "U1") (pin "32") (pinfunction "V8_6/B1+_32") (pintype "passive+no_connect"))
    )
    (net (code "128") (name "unconnected-(U1-V8_6{slash}VIN-0-Pad42)") (class "Default")
      (node (ref "U1") (pin "42") (pinfunction "V8_6/VIN-0_42") (pintype "passive+no_connect"))
    )
    (net (code "129") (name "unconnected-(U1-V8_7{slash}B1--Pad31)") (class "Default")
      (node (ref "U1") (pin "31") (pinfunction "V8_7/B1-_31") (pintype "passive+no_connect"))
    )
    (net (code "130") (name "unconnected-(U1-V8_7{slash}VIN+0-Pad41)") (class "Default")
      (node (ref "U1") (pin "41") (pinfunction "V8_7/VIN+0_41") (pintype "passive+no_connect"))
    )
    (net (code "131") (name "unconnected-(U1-VCLK{slash}AVS1-Pad40)") (class "Default")
      (node (ref "U1") (pin "40") (pinfunction "VCLK/AVS1_40") (pintype "passive+no_connect"))
    )
  )
)
